# 3_OUTPUT_RELAY.net
KiCad netlist of a schematic drawn in Altium Designer
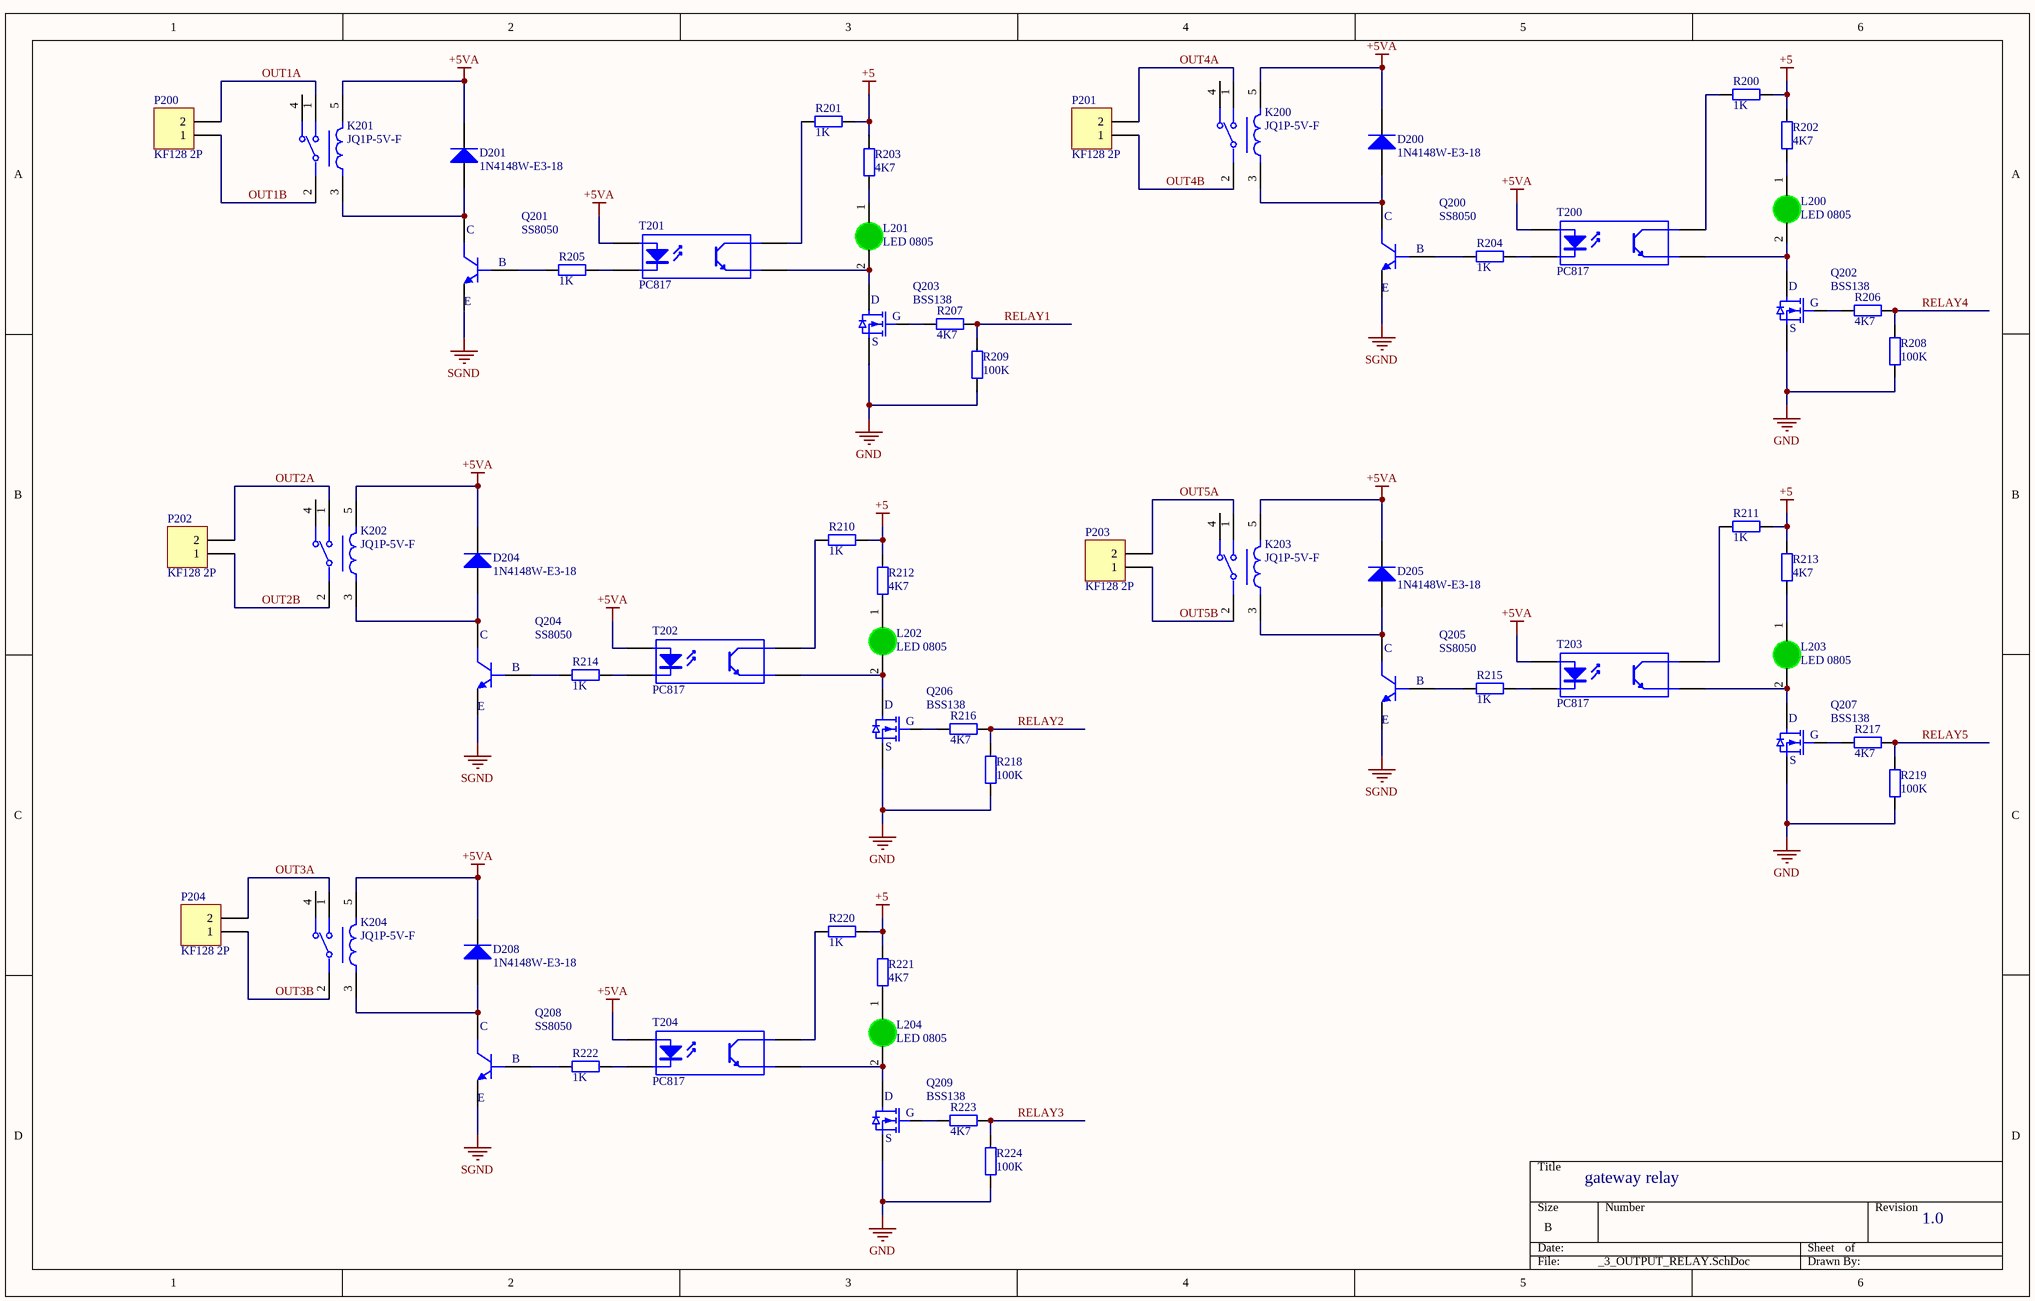
[diagram p0: _3_OUTPUT_RELAY.SchDoc]

(export (version "E")
  (design (tool "Eeschema 10.0.6"))
  (components
    (comp (ref "D200")
      (value "1N4148W-E3-18")
      (footprint "SOD-123")
      (description "DIODE GEN PURP 100V 300MA SOD123")
      (fields (field (name "MPN") "1N4148W-7-F") (field (name "MFR") "Diodes Incorporated"))
      (libsource (lib "BYTECH_HW_LIB_2019") (part "1N4148-W-7"))
    )
    (comp (ref "D201")
      (value "1N4148W-E3-18")
      (footprint "SOD-123")
      (description "DIODE GEN PURP 100V 300MA SOD123")
      (fields (field (name "MPN") "1N4148W-7-F") (field (name "MFR") "Diodes Incorporated"))
      (libsource (lib "BYTECH_HW_LIB_2019") (part "1N4148-W-7"))
    )
    (comp (ref "D204")
      (value "1N4148W-E3-18")
      (footprint "SOD-123")
      (description "DIODE GEN PURP 100V 300MA SOD123")
      (fields (field (name "MPN") "1N4148W-7-F") (field (name "MFR") "Diodes Incorporated"))
      (libsource (lib "BYTECH_HW_LIB_2019") (part "1N4148-W-7"))
    )
    (comp (ref "D205")
      (value "1N4148W-E3-18")
      (footprint "SOD-123")
      (description "DIODE GEN PURP 100V 300MA SOD123")
      (fields (field (name "MPN") "1N4148W-7-F") (field (name "MFR") "Diodes Incorporated"))
      (libsource (lib "BYTECH_HW_LIB_2019") (part "1N4148-W-7"))
    )
    (comp (ref "D208")
      (value "1N4148W-E3-18")
      (footprint "SOD-123")
      (description "DIODE GEN PURP 100V 300MA SOD123")
      (fields (field (name "MPN") "1N4148W-7-F") (field (name "MFR") "Diodes Incorporated"))
      (libsource (lib "BYTECH_HW_LIB_2019") (part "1N4148-W-7"))
    )
    (comp (ref "K200")
      (value "JQ1P-5V-F")
      (footprint "FP-JQ1P-5V-F-MFG")
      (description "RELAY GEN PURPOSE SPDT 10A 5V")
      (libsource (lib "Altium Content Vault") (part "0eb22fb5c08c907da7359f7111d0580"))
    )
    (comp (ref "K201")
      (value "JQ1P-5V-F")
      (footprint "FP-JQ1P-5V-F-MFG")
      (description "RELAY GEN PURPOSE SPDT 10A 5V")
      (libsource (lib "Altium Content Vault") (part "0eb22fb5c08c907da7359f7111d0580"))
    )
    (comp (ref "K202")
      (value "JQ1P-5V-F")
      (footprint "FP-JQ1P-5V-F-MFG")
      (description "RELAY GEN PURPOSE SPDT 10A 5V")
      (libsource (lib "Altium Content Vault") (part "0eb22fb5c08c907da7359f7111d0580"))
    )
    (comp (ref "K203")
      (value "JQ1P-5V-F")
      (footprint "FP-JQ1P-5V-F-MFG")
      (description "RELAY GEN PURPOSE SPDT 10A 5V")
      (libsource (lib "Altium Content Vault") (part "0eb22fb5c08c907da7359f7111d0580"))
    )
    (comp (ref "K204")
      (value "JQ1P-5V-F")
      (footprint "FP-JQ1P-5V-F-MFG")
      (description "RELAY GEN PURPOSE SPDT 10A 5V")
      (libsource (lib "Altium Content Vault") (part "0eb22fb5c08c907da7359f7111d0580"))
    )
    (comp (ref "L200")
      (value "LED 0805")
      (footprint "LED-0805-Green")
      (description "Dán")
      (libsource (lib "Altium_Lib_by_KhueNguyenCreator") (part "LED 0805 Xanh La"))
    )
    (comp (ref "L201")
      (value "LED 0805")
      (footprint "LED-0805-Green")
      (description "Dán")
      (libsource (lib "Altium_Lib_by_KhueNguyenCreator") (part "LED 0805 Xanh La"))
    )
    (comp (ref "L202")
      (value "LED 0805")
      (footprint "LED-0805-Green")
      (description "Dán")
      (libsource (lib "Altium_Lib_by_KhueNguyenCreator") (part "LED 0805 Xanh La"))
    )
    (comp (ref "L203")
      (value "LED 0805")
      (footprint "LED-0805-Green")
      (description "Dán")
      (libsource (lib "Altium_Lib_by_KhueNguyenCreator") (part "LED 0805 Xanh La"))
    )
    (comp (ref "L204")
      (value "LED 0805")
      (footprint "LED-0805-Green")
      (description "Dán")
      (libsource (lib "Altium_Lib_by_KhueNguyenCreator") (part "LED 0805 Xanh La"))
    )
    (comp (ref "P200")
      (value "KF128 2P")
      (footprint "KF128_2P")
      (description "Header, 2-Pin, pitch 5.08mm")
      (fields (field (name "MPN") "KF128-2P"))
      (libsource (lib "BYTECH_HW_LIB_2019") (part "KF128 2P"))
    )
    (comp (ref "P201")
      (value "KF128 2P")
      (footprint "KF128_2P")
      (description "Header, 2-Pin, pitch 5.08mm")
      (fields (field (name "MPN") "KF128-2P"))
      (libsource (lib "BYTECH_HW_LIB_2019") (part "KF128 2P"))
    )
    (comp (ref "P202")
      (value "KF128 2P")
      (footprint "KF128_2P")
      (description "Header, 2-Pin, pitch 5.08mm")
      (fields (field (name "MPN") "KF128-2P"))
      (libsource (lib "BYTECH_HW_LIB_2019") (part "KF128 2P"))
    )
    (comp (ref "P203")
      (value "KF128 2P")
      (footprint "KF128_2P")
      (description "Header, 2-Pin, pitch 5.08mm")
      (fields (field (name "MPN") "KF128-2P"))
      (libsource (lib "BYTECH_HW_LIB_2019") (part "KF128 2P"))
    )
    (comp (ref "P204")
      (value "KF128 2P")
      (footprint "KF128_2P")
      (description "Header, 2-Pin, pitch 5.08mm")
      (fields (field (name "MPN") "KF128-2P"))
      (libsource (lib "BYTECH_HW_LIB_2019") (part "KF128 2P"))
    )
    (comp (ref "Q200")
      (value "SS8050")
      (footprint "SOT23_3")
      (description "TRANS NPN 50V 0.15A SOT23-3")
      (fields (field (name "MPN") "2SC1815"))
      (libsource (lib "BYTECH_HW_LIB_2019") (part "2SC1815"))
    )
    (comp (ref "Q201")
      (value "SS8050")
      (footprint "SOT23_3")
      (description "TRANS NPN 50V 0.15A SOT23-3")
      (fields (field (name "MPN") "2SC1815"))
      (libsource (lib "BYTECH_HW_LIB_2019") (part "2SC1815"))
    )
    (comp (ref "Q202")
      (value "BSS138")
      (footprint "SOT23_3")
      (description "MOSFET N-CH 60V 300MA SOT-23")
      (fields (field (name "MPN") "2N7002,215"))
      (libsource (lib "BYTECH_HW_LIB_2019") (part "2N7002,215"))
    )
    (comp (ref "Q203")
      (value "BSS138")
      (footprint "SOT23_3")
      (description "MOSFET N-CH 60V 300MA SOT-23")
      (fields (field (name "MPN") "2N7002,215"))
      (libsource (lib "BYTECH_HW_LIB_2019") (part "2N7002,215"))
    )
    (comp (ref "Q204")
      (value "SS8050")
      (footprint "SOT23_3")
      (description "TRANS NPN 50V 0.15A SOT23-3")
      (fields (field (name "MPN") "2SC1815"))
      (libsource (lib "BYTECH_HW_LIB_2019") (part "2SC1815"))
    )
    (comp (ref "Q205")
      (value "SS8050")
      (footprint "SOT23_3")
      (description "TRANS NPN 50V 0.15A SOT23-3")
      (fields (field (name "MPN") "2SC1815"))
      (libsource (lib "BYTECH_HW_LIB_2019") (part "2SC1815"))
    )
    (comp (ref "Q206")
      (value "BSS138")
      (footprint "SOT23_3")
      (description "MOSFET N-CH 60V 300MA SOT-23")
      (fields (field (name "MPN") "2N7002,215"))
      (libsource (lib "BYTECH_HW_LIB_2019") (part "2N7002,215"))
    )
    (comp (ref "Q207")
      (value "BSS138")
      (footprint "SOT23_3")
      (description "MOSFET N-CH 60V 300MA SOT-23")
      (fields (field (name "MPN") "2N7002,215"))
      (libsource (lib "BYTECH_HW_LIB_2019") (part "2N7002,215"))
    )
    (comp (ref "Q208")
      (value "SS8050")
      (footprint "SOT23_3")
      (description "TRANS NPN 50V 0.15A SOT23-3")
      (fields (field (name "MPN") "2SC1815"))
      (libsource (lib "BYTECH_HW_LIB_2019") (part "2SC1815"))
    )
    (comp (ref "Q209")
      (value "BSS138")
      (footprint "SOT23_3")
      (description "MOSFET N-CH 60V 300MA SOT-23")
      (fields (field (name "MPN") "2N7002,215"))
      (libsource (lib "BYTECH_HW_LIB_2019") (part "2N7002,215"))
    )
    (comp (ref "R200")
      (value "1K")
      (footprint "RESC-0603 (1608)")
      (description "RES SMD 1 KOHM 1% 1/10W 0603")
      (fields (field (name "MPN") "RC0603FR-071KL"))
      (libsource (lib "BYTECH_HW_LIB_2019") (part "RC0603FR-071KL"))
    )
    (comp (ref "R201")
      (value "1K")
      (footprint "RESC-0603 (1608)")
      (description "RES SMD 1 KOHM 1% 1/10W 0603")
      (fields (field (name "MPN") "RC0603FR-071KL"))
      (libsource (lib "BYTECH_HW_LIB_2019") (part "RC0603FR-071KL"))
    )
    (comp (ref "R202")
      (value "4K7")
      (footprint "RESC-0603 (1608)")
      (description "RES SMD 4.7K OHM 1% 1/10W 0603")
      (fields (field (name "MPN") "RC0603FR-074K7L"))
      (libsource (lib "") (part "RC0603FR-074K7L_1"))
    )
    (comp (ref "R203")
      (value "4K7")
      (footprint "RESC-0603 (1608)")
      (description "RES SMD 4.7K OHM 1% 1/10W 0603")
      (fields (field (name "MPN") "RC0603FR-074K7L"))
      (libsource (lib "") (part "RC0603FR-074K7L_1"))
    )
    (comp (ref "R204")
      (value "1K")
      (footprint "RESC-0603 (1608)")
      (description "RES SMD 1 KOHM 1% 1/10W 0603")
      (fields (field (name "MPN") "RC0603FR-071KL"))
      (libsource (lib "BYTECH_HW_LIB_2019") (part "RC0603FR-071KL"))
    )
    (comp (ref "R205")
      (value "1K")
      (footprint "RESC-0603 (1608)")
      (description "RES SMD 1 KOHM 1% 1/10W 0603")
      (fields (field (name "MPN") "RC0603FR-071KL"))
      (libsource (lib "BYTECH_HW_LIB_2019") (part "RC0603FR-071KL"))
    )
    (comp (ref "R206")
      (value "4K7")
      (footprint "RESC-0603 (1608)")
      (description "RES SMD 4.7K OHM 1% 1/10W 0603")
      (fields (field (name "MPN") "RC0603FR-074K7L"))
      (libsource (lib "BYTECH_HW_LIB_2019") (part "RC0603FR-074K7L"))
    )
    (comp (ref "R207")
      (value "4K7")
      (footprint "RESC-0603 (1608)")
      (description "RES SMD 4.7K OHM 1% 1/10W 0603")
      (fields (field (name "MPN") "RC0603FR-074K7L"))
      (libsource (lib "BYTECH_HW_LIB_2019") (part "RC0603FR-074K7L"))
    )
    (comp (ref "R208")
      (value "100K")
      (footprint "RESC-0603 (1608)")
      (description "RES SMD 100K OHM 1% 1/10W 0603")
      (fields (field (name "MPN") "RC0603FR-07100KL"))
      (libsource (lib "BYTECH_HW_LIB_2019") (part "RC0603FR-07100KL"))
    )
    (comp (ref "R209")
      (value "100K")
      (footprint "RESC-0603 (1608)")
      (description "RES SMD 100K OHM 1% 1/10W 0603")
      (fields (field (name "MPN") "RC0603FR-07100KL"))
      (libsource (lib "BYTECH_HW_LIB_2019") (part "RC0603FR-07100KL"))
    )
    (comp (ref "R210")
      (value "1K")
      (footprint "RESC-0603 (1608)")
      (description "RES SMD 1 KOHM 1% 1/10W 0603")
      (fields (field (name "MPN") "RC0603FR-071KL"))
      (libsource (lib "BYTECH_HW_LIB_2019") (part "RC0603FR-071KL"))
    )
    (comp (ref "R211")
      (value "1K")
      (footprint "RESC-0603 (1608)")
      (description "RES SMD 1 KOHM 1% 1/10W 0603")
      (fields (field (name "MPN") "RC0603FR-071KL"))
      (libsource (lib "BYTECH_HW_LIB_2019") (part "RC0603FR-071KL"))
    )
    (comp (ref "R212")
      (value "4K7")
      (footprint "RESC-0603 (1608)")
      (description "RES SMD 4.7K OHM 1% 1/10W 0603")
      (fields (field (name "MPN") "RC0603FR-074K7L"))
      (libsource (lib "") (part "RC0603FR-074K7L_1"))
    )
    (comp (ref "R213")
      (value "4K7")
      (footprint "RESC-0603 (1608)")
      (description "RES SMD 4.7K OHM 1% 1/10W 0603")
      (fields (field (name "MPN") "RC0603FR-074K7L"))
      (libsource (lib "") (part "RC0603FR-074K7L_1"))
    )
    (comp (ref "R214")
      (value "1K")
      (footprint "RESC-0603 (1608)")
      (description "RES SMD 1 KOHM 1% 1/10W 0603")
      (fields (field (name "MPN") "RC0603FR-071KL"))
      (libsource (lib "BYTECH_HW_LIB_2019") (part "RC0603FR-071KL"))
    )
    (comp (ref "R215")
      (value "1K")
      (footprint "RESC-0603 (1608)")
      (description "RES SMD 1 KOHM 1% 1/10W 0603")
      (fields (field (name "MPN") "RC0603FR-071KL"))
      (libsource (lib "BYTECH_HW_LIB_2019") (part "RC0603FR-071KL"))
    )
    (comp (ref "R216")
      (value "4K7")
      (footprint "RESC-0603 (1608)")
      (description "RES SMD 4.7K OHM 1% 1/10W 0603")
      (fields (field (name "MPN") "RC0603FR-074K7L"))
      (libsource (lib "BYTECH_HW_LIB_2019") (part "RC0603FR-074K7L"))
    )
    (comp (ref "R217")
      (value "4K7")
      (footprint "RESC-0603 (1608)")
      (description "RES SMD 4.7K OHM 1% 1/10W 0603")
      (fields (field (name "MPN") "RC0603FR-074K7L"))
      (libsource (lib "BYTECH_HW_LIB_2019") (part "RC0603FR-074K7L"))
    )
    (comp (ref "R218")
      (value "100K")
      (footprint "RESC-0603 (1608)")
      (description "RES SMD 100K OHM 1% 1/10W 0603")
      (fields (field (name "MPN") "RC0603FR-07100KL"))
      (libsource (lib "BYTECH_HW_LIB_2019") (part "RC0603FR-07100KL"))
    )
    (comp (ref "R219")
      (value "100K")
      (footprint "RESC-0603 (1608)")
      (description "RES SMD 100K OHM 1% 1/10W 0603")
      (fields (field (name "MPN") "RC0603FR-07100KL"))
      (libsource (lib "BYTECH_HW_LIB_2019") (part "RC0603FR-07100KL"))
    )
    (comp (ref "R220")
      (value "1K")
      (footprint "RESC-0603 (1608)")
      (description "RES SMD 1 KOHM 1% 1/10W 0603")
      (fields (field (name "MPN") "RC0603FR-071KL"))
      (libsource (lib "BYTECH_HW_LIB_2019") (part "RC0603FR-071KL"))
    )
    (comp (ref "R221")
      (value "4K7")
      (footprint "RESC-0603 (1608)")
      (description "RES SMD 4.7K OHM 1% 1/10W 0603")
      (fields (field (name "MPN") "RC0603FR-074K7L"))
      (libsource (lib "") (part "RC0603FR-074K7L_1"))
    )
    (comp (ref "R222")
      (value "1K")
      (footprint "RESC-0603 (1608)")
      (description "RES SMD 1 KOHM 1% 1/10W 0603")
      (fields (field (name "MPN") "RC0603FR-071KL"))
      (libsource (lib "BYTECH_HW_LIB_2019") (part "RC0603FR-071KL"))
    )
    (comp (ref "R223")
      (value "4K7")
      (footprint "RESC-0603 (1608)")
      (description "RES SMD 4.7K OHM 1% 1/10W 0603")
      (fields (field (name "MPN") "RC0603FR-074K7L"))
      (libsource (lib "BYTECH_HW_LIB_2019") (part "RC0603FR-074K7L"))
    )
    (comp (ref "R224")
      (value "100K")
      (footprint "RESC-0603 (1608)")
      (description "RES SMD 100K OHM 1% 1/10W 0603")
      (fields (field (name "MPN") "RC0603FR-07100KL"))
      (libsource (lib "BYTECH_HW_LIB_2019") (part "RC0603FR-07100KL"))
    )
    (comp (ref "T200")
      (value "PC817")
      (footprint "OPTO TRANSISTOR_SMD-4")
      (description "OPTOISOLATOR 5KV TRANSISTOR 4SMD")
      (fields (field (name "MPN") "HCPL-817-500E"))
      (libsource (lib "BYTECH_HW_LIB_2019") (part "HCPL-817-500E"))
    )
    (comp (ref "T201")
      (value "PC817")
      (footprint "OPTO TRANSISTOR_SMD-4")
      (description "OPTOISOLATOR 5KV TRANSISTOR 4SMD")
      (fields (field (name "MPN") "HCPL-817-500E"))
      (libsource (lib "BYTECH_HW_LIB_2019") (part "HCPL-817-500E"))
    )
    (comp (ref "T202")
      (value "PC817")
      (footprint "OPTO TRANSISTOR_SMD-4")
      (description "OPTOISOLATOR 5KV TRANSISTOR 4SMD")
      (fields (field (name "MPN") "HCPL-817-500E"))
      (libsource (lib "BYTECH_HW_LIB_2019") (part "HCPL-817-500E"))
    )
    (comp (ref "T203")
      (value "PC817")
      (footprint "OPTO TRANSISTOR_SMD-4")
      (description "OPTOISOLATOR 5KV TRANSISTOR 4SMD")
      (fields (field (name "MPN") "HCPL-817-500E"))
      (libsource (lib "BYTECH_HW_LIB_2019") (part "HCPL-817-500E"))
    )
    (comp (ref "T204")
      (value "PC817")
      (footprint "OPTO TRANSISTOR_SMD-4")
      (description "OPTOISOLATOR 5KV TRANSISTOR 4SMD")
      (fields (field (name "MPN") "HCPL-817-500E"))
      (libsource (lib "BYTECH_HW_LIB_2019") (part "HCPL-817-500E"))
    )
  )
  (nets
    (net (code "1") (name "+5") (class "Default")
      (node (ref "R200") (pin "2") (pinfunction "2_2") (pintype "passive"))
      (node (ref "R201") (pin "2") (pinfunction "2_2") (pintype "passive"))
      (node (ref "R202") (pin "2") (pinfunction "2_2") (pintype "passive"))
      (node (ref "R203") (pin "2") (pinfunction "2_2") (pintype "passive"))
      (node (ref "R210") (pin "2") (pinfunction "2_2") (pintype "passive"))
      (node (ref "R211") (pin "2") (pinfunction "2_2") (pintype "passive"))
      (node (ref "R212") (pin "2") (pinfunction "2_2") (pintype "passive"))
      (node (ref "R213") (pin "2") (pinfunction "2_2") (pintype "passive"))
      (node (ref "R220") (pin "2") (pinfunction "2_2") (pintype "passive"))
      (node (ref "R221") (pin "2") (pinfunction "2_2") (pintype "passive"))
    )
    (net (code "2") (name "+5VA") (class "Default")
      (node (ref "D200") (pin "2") (pinfunction "K_2") (pintype "passive"))
      (node (ref "D201") (pin "2") (pinfunction "K_2") (pintype "passive"))
      (node (ref "D204") (pin "2") (pinfunction "K_2") (pintype "passive"))
      (node (ref "D205") (pin "2") (pinfunction "K_2") (pintype "passive"))
      (node (ref "D208") (pin "2") (pinfunction "K_2") (pintype "passive"))
      (node (ref "K200") (pin "5") (pinfunction "2_COIL_5") (pintype "passive"))
      (node (ref "K201") (pin "5") (pinfunction "2_COIL_5") (pintype "passive"))
      (node (ref "K202") (pin "5") (pinfunction "2_COIL_5") (pintype "passive"))
      (node (ref "K203") (pin "5") (pinfunction "2_COIL_5") (pintype "passive"))
      (node (ref "K204") (pin "5") (pinfunction "2_COIL_5") (pintype "passive"))
      (node (ref "T200") (pin "1") (pinfunction "1_1") (pintype "passive"))
      (node (ref "T201") (pin "1") (pinfunction "1_1") (pintype "passive"))
      (node (ref "T202") (pin "1") (pinfunction "1_1") (pintype "passive"))
      (node (ref "T203") (pin "1") (pinfunction "1_1") (pintype "passive"))
      (node (ref "T204") (pin "1") (pinfunction "1_1") (pintype "passive"))
    )
    (net (code "3") (name "/OUT1A") (class "Default")
      (node (ref "K201") (pin "1") (pinfunction "N.O._1") (pintype "passive"))
      (node (ref "P200") (pin "2") (pinfunction "2_2") (pintype "passive"))
    )
    (net (code "4") (name "/OUT1B") (class "Default")
      (node (ref "K201") (pin "2") (pinfunction "COM_2") (pintype "passive"))
      (node (ref "P200") (pin "1") (pinfunction "1_1") (pintype "passive"))
    )
    (net (code "5") (name "/OUT2A") (class "Default")
      (node (ref "K202") (pin "1") (pinfunction "N.O._1") (pintype "passive"))
      (node (ref "P202") (pin "2") (pinfunction "2_2") (pintype "passive"))
    )
    (net (code "6") (name "/OUT2B") (class "Default")
      (node (ref "K202") (pin "2") (pinfunction "COM_2") (pintype "passive"))
      (node (ref "P202") (pin "1") (pinfunction "1_1") (pintype "passive"))
    )
    (net (code "7") (name "/OUT3A") (class "Default")
      (node (ref "K204") (pin "1") (pinfunction "N.O._1") (pintype "passive"))
      (node (ref "P204") (pin "2") (pinfunction "2_2") (pintype "passive"))
    )
    (net (code "8") (name "/OUT3B") (class "Default")
      (node (ref "K204") (pin "2") (pinfunction "COM_2") (pintype "passive"))
      (node (ref "P204") (pin "1") (pinfunction "1_1") (pintype "passive"))
    )
    (net (code "9") (name "/OUT4A") (class "Default")
      (node (ref "K200") (pin "1") (pinfunction "N.O._1") (pintype "passive"))
      (node (ref "P201") (pin "2") (pinfunction "2_2") (pintype "passive"))
    )
    (net (code "10") (name "/OUT4B") (class "Default")
      (node (ref "K200") (pin "2") (pinfunction "COM_2") (pintype "passive"))
      (node (ref "P201") (pin "1") (pinfunction "1_1") (pintype "passive"))
    )
    (net (code "11") (name "/OUT5A") (class "Default")
      (node (ref "K203") (pin "1") (pinfunction "N.O._1") (pintype "passive"))
      (node (ref "P203") (pin "2") (pinfunction "2_2") (pintype "passive"))
    )
    (net (code "12") (name "/OUT5B") (class "Default")
      (node (ref "K203") (pin "2") (pinfunction "COM_2") (pintype "passive"))
      (node (ref "P203") (pin "1") (pinfunction "1_1") (pintype "passive"))
    )
    (net (code "13") (name "/RELAY1") (class "Default")
      (node (ref "R207") (pin "1") (pinfunction "1_1") (pintype "passive"))
      (node (ref "R209") (pin "2") (pinfunction "2_2") (pintype "passive"))
    )
    (net (code "14") (name "/RELAY2") (class "Default")
      (node (ref "R216") (pin "1") (pinfunction "1_1") (pintype "passive"))
      (node (ref "R218") (pin "2") (pinfunction "2_2") (pintype "passive"))
    )
    (net (code "15") (name "/RELAY3") (class "Default")
      (node (ref "R223") (pin "1") (pinfunction "1_1") (pintype "passive"))
      (node (ref "R224") (pin "2") (pinfunction "2_2") (pintype "passive"))
    )
    (net (code "16") (name "/RELAY4") (class "Default")
      (node (ref "R206") (pin "1") (pinfunction "1_1") (pintype "passive"))
      (node (ref "R208") (pin "2") (pinfunction "2_2") (pintype "passive"))
    )
    (net (code "17") (name "/RELAY5") (class "Default")
      (node (ref "R217") (pin "1") (pinfunction "1_1") (pintype "passive"))
      (node (ref "R219") (pin "2") (pinfunction "2_2") (pintype "passive"))
    )
    (net (code "18") (name "GND") (class "Default")
      (node (ref "Q202") (pin "2") (pinfunction "S_2") (pintype "passive"))
      (node (ref "Q203") (pin "2") (pinfunction "S_2") (pintype "passive"))
      (node (ref "Q206") (pin "2") (pinfunction "S_2") (pintype "passive"))
      (node (ref "Q207") (pin "2") (pinfunction "S_2") (pintype "passive"))
      (node (ref "Q209") (pin "2") (pinfunction "S_2") (pintype "passive"))
      (node (ref "R208") (pin "1") (pinfunction "1_1") (pintype "passive"))
      (node (ref "R209") (pin "1") (pinfunction "1_1") (pintype "passive"))
      (node (ref "R218") (pin "1") (pinfunction "1_1") (pintype "passive"))
      (node (ref "R219") (pin "1") (pinfunction "1_1") (pintype "passive"))
      (node (ref "R224") (pin "1") (pinfunction "1_1") (pintype "passive"))
    )
    (net (code "19") (name "Net-(D200-A)") (class "Default")
      (node (ref "D200") (pin "1") (pinfunction "A_1") (pintype "passive"))
      (node (ref "K200") (pin "3") (pinfunction "1_COIL_3") (pintype "passive"))
      (node (ref "Q200") (pin "3") (pinfunction "C_3") (pintype "passive"))
    )
    (net (code "20") (name "Net-(D201-A)") (class "Default")
      (node (ref "D201") (pin "1") (pinfunction "A_1") (pintype "passive"))
      (node (ref "K201") (pin "3") (pinfunction "1_COIL_3") (pintype "passive"))
      (node (ref "Q201") (pin "3") (pinfunction "C_3") (pintype "passive"))
    )
    (net (code "21") (name "Net-(D204-A)") (class "Default")
      (node (ref "D204") (pin "1") (pinfunction "A_1") (pintype "passive"))
      (node (ref "K202") (pin "3") (pinfunction "1_COIL_3") (pintype "passive"))
      (node (ref "Q204") (pin "3") (pinfunction "C_3") (pintype "passive"))
    )
    (net (code "22") (name "Net-(D205-A)") (class "Default")
      (node (ref "D205") (pin "1") (pinfunction "A_1") (pintype "passive"))
      (node (ref "K203") (pin "3") (pinfunction "1_COIL_3") (pintype "passive"))
      (node (ref "Q205") (pin "3") (pinfunction "C_3") (pintype "passive"))
    )
    (net (code "23") (name "Net-(D208-A)") (class "Default")
      (node (ref "D208") (pin "1") (pinfunction "A_1") (pintype "passive"))
      (node (ref "K204") (pin "3") (pinfunction "1_COIL_3") (pintype "passive"))
      (node (ref "Q208") (pin "3") (pinfunction "C_3") (pintype "passive"))
    )
    (net (code "24") (name "Net-(L200-A)") (class "Default")
      (node (ref "L200") (pin "1") (pinfunction "A_1") (pintype "passive"))
      (node (ref "R202") (pin "1") (pinfunction "1_1") (pintype "passive"))
    )
    (net (code "25") (name "Net-(L200-K)") (class "Default")
      (node (ref "L200") (pin "2") (pinfunction "K_2") (pintype "passive"))
      (node (ref "Q202") (pin "3") (pinfunction "D_3") (pintype "passive"))
      (node (ref "T200") (pin "3") (pinfunction "3_3") (pintype "passive"))
    )
    (net (code "26") (name "Net-(L201-A)") (class "Default")
      (node (ref "L201") (pin "1") (pinfunction "A_1") (pintype "passive"))
      (node (ref "R203") (pin "1") (pinfunction "1_1") (pintype "passive"))
    )
    (net (code "27") (name "Net-(L201-K)") (class "Default")
      (node (ref "L201") (pin "2") (pinfunction "K_2") (pintype "passive"))
      (node (ref "Q203") (pin "3") (pinfunction "D_3") (pintype "passive"))
      (node (ref "T201") (pin "3") (pinfunction "3_3") (pintype "passive"))
    )
    (net (code "28") (name "Net-(L202-A)") (class "Default")
      (node (ref "L202") (pin "1") (pinfunction "A_1") (pintype "passive"))
      (node (ref "R212") (pin "1") (pinfunction "1_1") (pintype "passive"))
    )
    (net (code "29") (name "Net-(L202-K)") (class "Default")
      (node (ref "L202") (pin "2") (pinfunction "K_2") (pintype "passive"))
      (node (ref "Q206") (pin "3") (pinfunction "D_3") (pintype "passive"))
      (node (ref "T202") (pin "3") (pinfunction "3_3") (pintype "passive"))
    )
    (net (code "30") (name "Net-(L203-A)") (class "Default")
      (node (ref "L203") (pin "1") (pinfunction "A_1") (pintype "passive"))
      (node (ref "R213") (pin "1") (pinfunction "1_1") (pintype "passive"))
    )
    (net (code "31") (name "Net-(L203-K)") (class "Default")
      (node (ref "L203") (pin "2") (pinfunction "K_2") (pintype "passive"))
      (node (ref "Q207") (pin "3") (pinfunction "D_3") (pintype "passive"))
      (node (ref "T203") (pin "3") (pinfunction "3_3") (pintype "passive"))
    )
    (net (code "32") (name "Net-(L204-A)") (class "Default")
      (node (ref "L204") (pin "1") (pinfunction "A_1") (pintype "passive"))
      (node (ref "R221") (pin "1") (pinfunction "1_1") (pintype "passive"))
    )
    (net (code "33") (name "Net-(L204-K)") (class "Default")
      (node (ref "L204") (pin "2") (pinfunction "K_2") (pintype "passive"))
      (node (ref "Q209") (pin "3") (pinfunction "D_3") (pintype "passive"))
      (node (ref "T204") (pin "3") (pinfunction "3_3") (pintype "passive"))
    )
    (net (code "34") (name "Net-(Q200-B)") (class "Default")
      (node (ref "Q200") (pin "1") (pinfunction "B_1") (pintype "passive"))
      (node (ref "R204") (pin "1") (pinfunction "1_1") (pintype "passive"))
    )
    (net (code "35") (name "Net-(Q201-B)") (class "Default")
      (node (ref "Q201") (pin "1") (pinfunction "B_1") (pintype "passive"))
      (node (ref "R205") (pin "1") (pinfunction "1_1") (pintype "passive"))
    )
    (net (code "36") (name "Net-(Q202-G)") (class "Default")
      (node (ref "Q202") (pin "1") (pinfunction "G_1") (pintype "passive"))
      (node (ref "R206") (pin "2") (pinfunction "2_2") (pintype "passive"))
    )
    (net (code "37") (name "Net-(Q203-G)") (class "Default")
      (node (ref "Q203") (pin "1") (pinfunction "G_1") (pintype "passive"))
      (node (ref "R207") (pin "2") (pinfunction "2_2") (pintype "passive"))
    )
    (net (code "38") (name "Net-(Q204-B)") (class "Default")
      (node (ref "Q204") (pin "1") (pinfunction "B_1") (pintype "passive"))
      (node (ref "R214") (pin "1") (pinfunction "1_1") (pintype "passive"))
    )
    (net (code "39") (name "Net-(Q205-B)") (class "Default")
      (node (ref "Q205") (pin "1") (pinfunction "B_1") (pintype "passive"))
      (node (ref "R215") (pin "1") (pinfunction "1_1") (pintype "passive"))
    )
    (net (code "40") (name "Net-(Q206-G)") (class "Default")
      (node (ref "Q206") (pin "1") (pinfunction "G_1") (pintype "passive"))
      (node (ref "R216") (pin "2") (pinfunction "2_2") (pintype "passive"))
    )
    (net (code "41") (name "Net-(Q207-G)") (class "Default")
      (node (ref "Q207") (pin "1") (pinfunction "G_1") (pintype "passive"))
      (node (ref "R217") (pin "2") (pinfunction "2_2") (pintype "passive"))
    )
    (net (code "42") (name "Net-(Q208-B)") (class "Default")
      (node (ref "Q208") (pin "1") (pinfunction "B_1") (pintype "passive"))
      (node (ref "R222") (pin "1") (pinfunction "1_1") (pintype "passive"))
    )
    (net (code "43") (name "Net-(Q209-G)") (class "Default")
      (node (ref "Q209") (pin "1") (pinfunction "G_1") (pintype "passive"))
      (node (ref "R223") (pin "2") (pinfunction "2_2") (pintype "passive"))
    )
    (net (code "44") (name "Net-(R200-Pad1)") (class "Default")
      (node (ref "R200") (pin "1") (pinfunction "1_1") (pintype "passive"))
      (node (ref "T200") (pin "4") (pinfunction "4_4") (pintype "passive"))
    )
    (net (code "45") (name "Net-(R201-Pad1)") (class "Default")
      (node (ref "R201") (pin "1") (pinfunction "1_1") (pintype "passive"))
      (node (ref "T201") (pin "4") (pinfunction "4_4") (pintype "passive"))
    )
    (net (code "46") (name "Net-(R204-Pad2)") (class "Default")
      (node (ref "R204") (pin "2") (pinfunction "2_2") (pintype "passive"))
      (node (ref "T200") (pin "2") (pinfunction "2_2") (pintype "passive"))
    )
    (net (code "47") (name "Net-(R205-Pad2)") (class "Default")
      (node (ref "R205") (pin "2") (pinfunction "2_2") (pintype "passive"))
      (node (ref "T201") (pin "2") (pinfunction "2_2") (pintype "passive"))
    )
    (net (code "48") (name "Net-(R210-Pad1)") (class "Default")
      (node (ref "R210") (pin "1") (pinfunction "1_1") (pintype "passive"))
      (node (ref "T202") (pin "4") (pinfunction "4_4") (pintype "passive"))
    )
    (net (code "49") (name "Net-(R211-Pad1)") (class "Default")
      (node (ref "R211") (pin "1") (pinfunction "1_1") (pintype "passive"))
      (node (ref "T203") (pin "4") (pinfunction "4_4") (pintype "passive"))
    )
    (net (code "50") (name "Net-(R214-Pad2)") (class "Default")
      (node (ref "R214") (pin "2") (pinfunction "2_2") (pintype "passive"))
      (node (ref "T202") (pin "2") (pinfunction "2_2") (pintype "passive"))
    )
    (net (code "51") (name "Net-(R215-Pad2)") (class "Default")
      (node (ref "R215") (pin "2") (pinfunction "2_2") (pintype "passive"))
      (node (ref "T203") (pin "2") (pinfunction "2_2") (pintype "passive"))
    )
    (net (code "52") (name "Net-(R220-Pad1)") (class "Default")
      (node (ref "R220") (pin "1") (pinfunction "1_1") (pintype "passive"))
      (node (ref "T204") (pin "4") (pinfunction "4_4") (pintype "passive"))
    )
    (net (code "53") (name "Net-(R222-Pad2)") (class "Default")
      (node (ref "R222") (pin "2") (pinfunction "2_2") (pintype "passive"))
      (node (ref "T204") (pin "2") (pinfunction "2_2") (pintype "passive"))
    )
    (net (code "54") (name "SGND") (class "Default")
      (node (ref "Q200") (pin "2") (pinfunction "E_2") (pintype "passive"))
      (node (ref "Q201") (pin "2") (pinfunction "E_2") (pintype "passive"))
      (node (ref "Q204") (pin "2") (pinfunction "E_2") (pintype "passive"))
      (node (ref "Q205") (pin "2") (pinfunction "E_2") (pintype "passive"))
      (node (ref "Q208") (pin "2") (pinfunction "E_2") (pintype "passive"))
    )
    (net (code "55") (name "unconnected-(K200-N.C.-Pad4)") (class "Default")
      (node (ref "K200") (pin "4") (pinfunction "N.C._4") (pintype "passive"))
    )
    (net (code "56") (name "unconnected-(K201-N.C.-Pad4)") (class "Default")
      (node (ref "K201") (pin "4") (pinfunction "N.C._4") (pintype "passive"))
    )
    (net (code "57") (name "unconnected-(K202-N.C.-Pad4)") (class "Default")
      (node (ref "K202") (pin "4") (pinfunction "N.C._4") (pintype "passive"))
    )
    (net (code "58") (name "unconnected-(K203-N.C.-Pad4)") (class "Default")
      (node (ref "K203") (pin "4") (pinfunction "N.C._4") (pintype "passive"))
    )
    (net (code "59") (name "unconnected-(K204-N.C.-Pad4)") (class "Default")
      (node (ref "K204") (pin "4") (pinfunction "N.C._4") (pintype "passive"))
    )
  )
)
